# oled-lpc81x.net
KiCad netlist of a schematic drawn in EAGLE
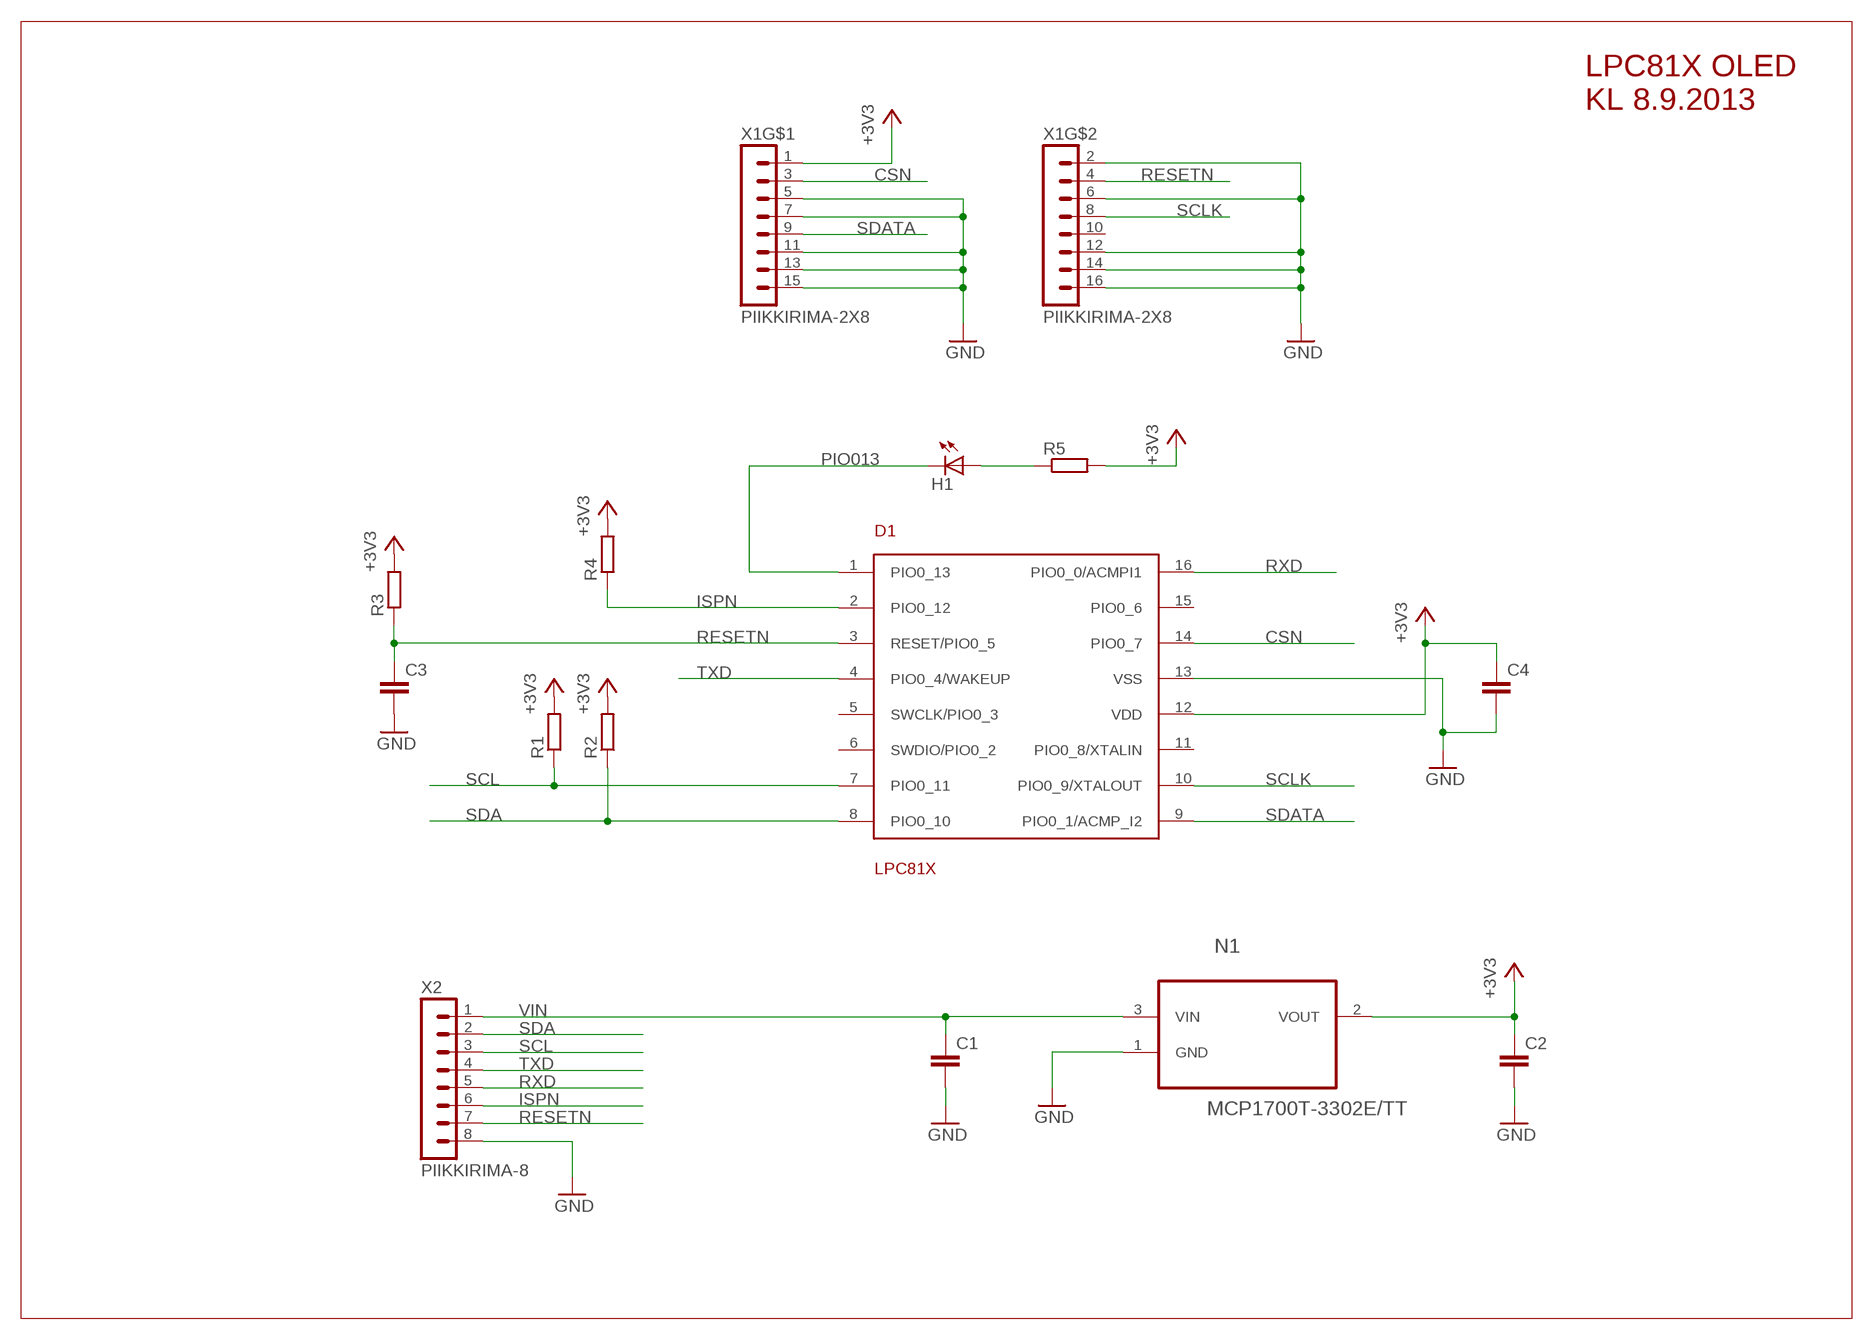
[diagram p0: schematic, sheet 1]

(export (version "E")
  (design (tool "Eeschema 10.0.6"))
  (components
    (comp (ref "C1")
      (value "C-EUC0805")
      (footprint "eagle-import:C0805")
      (libsource (lib "eagle-import") (part "C-EUC0805"))
    )
    (comp (ref "C2")
      (value "C-EUC0805")
      (footprint "eagle-import:C0805")
      (libsource (lib "eagle-import") (part "C-EUC0805"))
    )
    (comp (ref "C3")
      (value "C-EUC0603")
      (footprint "eagle-import:C0603")
      (libsource (lib "eagle-import") (part "C-EUC0603"))
    )
    (comp (ref "C4")
      (value "C-EUC0805")
      (footprint "eagle-import:C0805")
      (libsource (lib "eagle-import") (part "C-EUC0805"))
    )
    (comp (ref "D1")
      (value "LPC81X")
      (footprint "eagle-import:TSSOP16")
      (libsource (lib "eagle-import") (part "LPC81X"))
    )
    (comp (ref "H1")
      (value "LEDCHIP-LED0603")
      (footprint "eagle-import:CHIP-LED0603")
      (libsource (lib "eagle-import") (part "LEDCHIP-LED0603"))
    )
    (comp (ref "N1")
      (value "MCP1700T-3302E/TT")
      (footprint "eagle-import:SOT95P237X112-3N")
      (libsource (lib "eagle-import") (part "MCP1700T-3302E/TT"))
    )
    (comp (ref "R1")
      (value "R-EU_R0603")
      (footprint "eagle-import:R0603")
      (libsource (lib "eagle-import") (part "R-EU_R0603"))
    )
    (comp (ref "R2")
      (value "R-EU_R0603")
      (footprint "eagle-import:R0603")
      (libsource (lib "eagle-import") (part "R-EU_R0603"))
    )
    (comp (ref "R3")
      (value "R-EU_R0603")
      (footprint "eagle-import:R0603")
      (libsource (lib "eagle-import") (part "R-EU_R0603"))
    )
    (comp (ref "R4")
      (value "R-EU_R0603")
      (footprint "eagle-import:R0603")
      (libsource (lib "eagle-import") (part "R-EU_R0603"))
    )
    (comp (ref "R5")
      (value "R-EU_R0603")
      (footprint "eagle-import:R0603")
      (libsource (lib "eagle-import") (part "R-EU_R0603"))
    )
    (comp (ref "X1")
      (value "PIIKKIRIMA-2X8")
      (footprint "eagle-import:PIIKKIRIMA-2X8")
      (libsource (lib "eagle-import") (part "PIIKKIRIMA-2X8"))
    )
    (comp (ref "X2")
      (value "PIIKKIRIMA-8")
      (footprint "eagle-import:PIIKKIRIMA-8")
      (libsource (lib "eagle-import") (part "PIIKKIRIMA-8"))
    )
  )
  (nets
    (net (code "1") (name "+3V3") (class "Default")
      (node (ref "C2") (pin "1") (pinfunction "1_1") (pintype "passive"))
      (node (ref "C4") (pin "1") (pinfunction "1_1") (pintype "passive"))
      (node (ref "D1") (pin "12") (pinfunction "VDD_12") (pintype "bidirectional"))
      (node (ref "N1") (pin "2") (pinfunction "VOUT_2") (pintype "output"))
      (node (ref "R1") (pin "2") (pinfunction "2_2") (pintype "passive"))
      (node (ref "R2") (pin "2") (pinfunction "2_2") (pintype "passive"))
      (node (ref "R3") (pin "2") (pinfunction "2_2") (pintype "passive"))
      (node (ref "R4") (pin "2") (pinfunction "2_2") (pintype "passive"))
      (node (ref "R5") (pin "2") (pinfunction "2_2") (pintype "passive"))
      (node (ref "X1") (pin "1") (pinfunction "1_1") (pintype "passive"))
    )
    (net (code "2") (name "/CSN") (class "Default")
      (node (ref "D1") (pin "14") (pinfunction "PIO0_7_14") (pintype "bidirectional"))
      (node (ref "X1") (pin "3") (pinfunction "2_3") (pintype "passive"))
    )
    (net (code "3") (name "/ISPN") (class "Default")
      (node (ref "D1") (pin "2") (pinfunction "PIO0_12_2") (pintype "bidirectional"))
      (node (ref "R4") (pin "1") (pinfunction "1_1") (pintype "passive"))
      (node (ref "X2") (pin "6") (pinfunction "6_6") (pintype "passive"))
    )
    (net (code "4") (name "/PIO013") (class "Default")
      (node (ref "D1") (pin "1") (pinfunction "PIO0_13_1") (pintype "bidirectional"))
      (node (ref "H1") (pin "C") (pinfunction "C_C") (pintype "passive"))
    )
    (net (code "5") (name "/RESETN") (class "Default")
      (node (ref "C3") (pin "1") (pinfunction "1_1") (pintype "passive"))
      (node (ref "D1") (pin "3") (pinfunction "RESET/PIO0_5_3") (pintype "bidirectional"))
      (node (ref "R3") (pin "1") (pinfunction "1_1") (pintype "passive"))
      (node (ref "X1") (pin "4") (pinfunction "2_4") (pintype "passive"))
      (node (ref "X2") (pin "7") (pinfunction "7_7") (pintype "passive"))
    )
    (net (code "6") (name "/RXD") (class "Default")
      (node (ref "D1") (pin "16") (pinfunction "PIO0_0/ACMPI1_16") (pintype "bidirectional"))
      (node (ref "X2") (pin "5") (pinfunction "5_5") (pintype "passive"))
    )
    (net (code "7") (name "/SCL") (class "Default")
      (node (ref "D1") (pin "7") (pinfunction "PIO0_11_7") (pintype "bidirectional"))
      (node (ref "R1") (pin "1") (pinfunction "1_1") (pintype "passive"))
      (node (ref "X2") (pin "3") (pinfunction "3_3") (pintype "passive"))
    )
    (net (code "8") (name "/SCLK") (class "Default")
      (node (ref "D1") (pin "10") (pinfunction "PIO0_9/XTALOUT_10") (pintype "bidirectional"))
      (node (ref "X1") (pin "8") (pinfunction "4_8") (pintype "passive"))
    )
    (net (code "9") (name "/SDA") (class "Default")
      (node (ref "D1") (pin "8") (pinfunction "PIO0_10_8") (pintype "bidirectional"))
      (node (ref "R2") (pin "1") (pinfunction "1_1") (pintype "passive"))
      (node (ref "X2") (pin "2") (pinfunction "2_2") (pintype "passive"))
    )
    (net (code "10") (name "/SDATA") (class "Default")
      (node (ref "D1") (pin "9") (pinfunction "PIO0_1/ACMP_I2_9") (pintype "bidirectional"))
      (node (ref "X1") (pin "9") (pinfunction "5_9") (pintype "passive"))
    )
    (net (code "11") (name "/TXD") (class "Default")
      (node (ref "D1") (pin "4") (pinfunction "PIO0_4/WAKEUP_4") (pintype "bidirectional"))
      (node (ref "X2") (pin "4") (pinfunction "4_4") (pintype "passive"))
    )
    (net (code "12") (name "/VIN") (class "Default")
      (node (ref "C1") (pin "1") (pinfunction "1_1") (pintype "passive"))
      (node (ref "N1") (pin "3") (pinfunction "VIN_3") (pintype "input"))
      (node (ref "X2") (pin "1") (pinfunction "1_1") (pintype "passive"))
    )
    (net (code "13") (name "GND") (class "Default")
      (node (ref "C1") (pin "2") (pinfunction "2_2") (pintype "passive"))
      (node (ref "C2") (pin "2") (pinfunction "2_2") (pintype "passive"))
      (node (ref "C3") (pin "2") (pinfunction "2_2") (pintype "passive"))
      (node (ref "C4") (pin "2") (pinfunction "2_2") (pintype "passive"))
      (node (ref "D1") (pin "13") (pinfunction "VSS_13") (pintype "bidirectional"))
      (node (ref "N1") (pin "1") (pinfunction "GND_1") (pintype "passive"))
      (node (ref "X1") (pin "11") (pinfunction "6_11") (pintype "passive"))
      (node (ref "X1") (pin "12") (pinfunction "6_12") (pintype "passive"))
      (node (ref "X1") (pin "13") (pinfunction "7_13") (pintype "passive"))
      (node (ref "X1") (pin "14") (pinfunction "7_14") (pintype "passive"))
      (node (ref "X1") (pin "15") (pinfunction "8_15") (pintype "passive"))
      (node (ref "X1") (pin "16") (pinfunction "8_16") (pintype "passive"))
      (node (ref "X1") (pin "2") (pinfunction "1_2") (pintype "passive"))
      (node (ref "X1") (pin "5") (pinfunction "3_5") (pintype "passive"))
      (node (ref "X1") (pin "6") (pinfunction "3_6") (pintype "passive"))
      (node (ref "X1") (pin "7") (pinfunction "4_7") (pintype "passive"))
      (node (ref "X2") (pin "8") (pinfunction "8_8") (pintype "passive"))
    )
    (net (code "14") (name "Net-(H1-PadA)") (class "Default")
      (node (ref "H1") (pin "A") (pinfunction "A_A") (pintype "passive"))
      (node (ref "R5") (pin "1") (pinfunction "1_1") (pintype "passive"))
    )
    (net (code "15") (name "unconnected-(D1-PIO0_6-Pad15)") (class "Default")
      (node (ref "D1") (pin "15") (pinfunction "PIO0_6_15") (pintype "bidirectional"))
    )
    (net (code "16") (name "unconnected-(D1-PIO0_8{slash}XTALIN-Pad11)") (class "Default")
      (node (ref "D1") (pin "11") (pinfunction "PIO0_8/XTALIN_11") (pintype "bidirectional"))
    )
    (net (code "17") (name "unconnected-(D1-SWCLK{slash}PIO0_3-Pad5)") (class "Default")
      (node (ref "D1") (pin "5") (pinfunction "SWCLK/PIO0_3_5") (pintype "bidirectional"))
    )
    (net (code "18") (name "unconnected-(D1-SWDIO{slash}PIO0_2-Pad6)") (class "Default")
      (node (ref "D1") (pin "6") (pinfunction "SWDIO/PIO0_2_6") (pintype "bidirectional"))
    )
    (net (code "19") (name "unconnected-(X1B-5-Pad10)") (class "Default")
      (node (ref "X1") (pin "10") (pinfunction "5_10") (pintype "passive"))
    )
  )
)
